# untitled.net
KiCad netlist of a schematic drawn in EAGLE
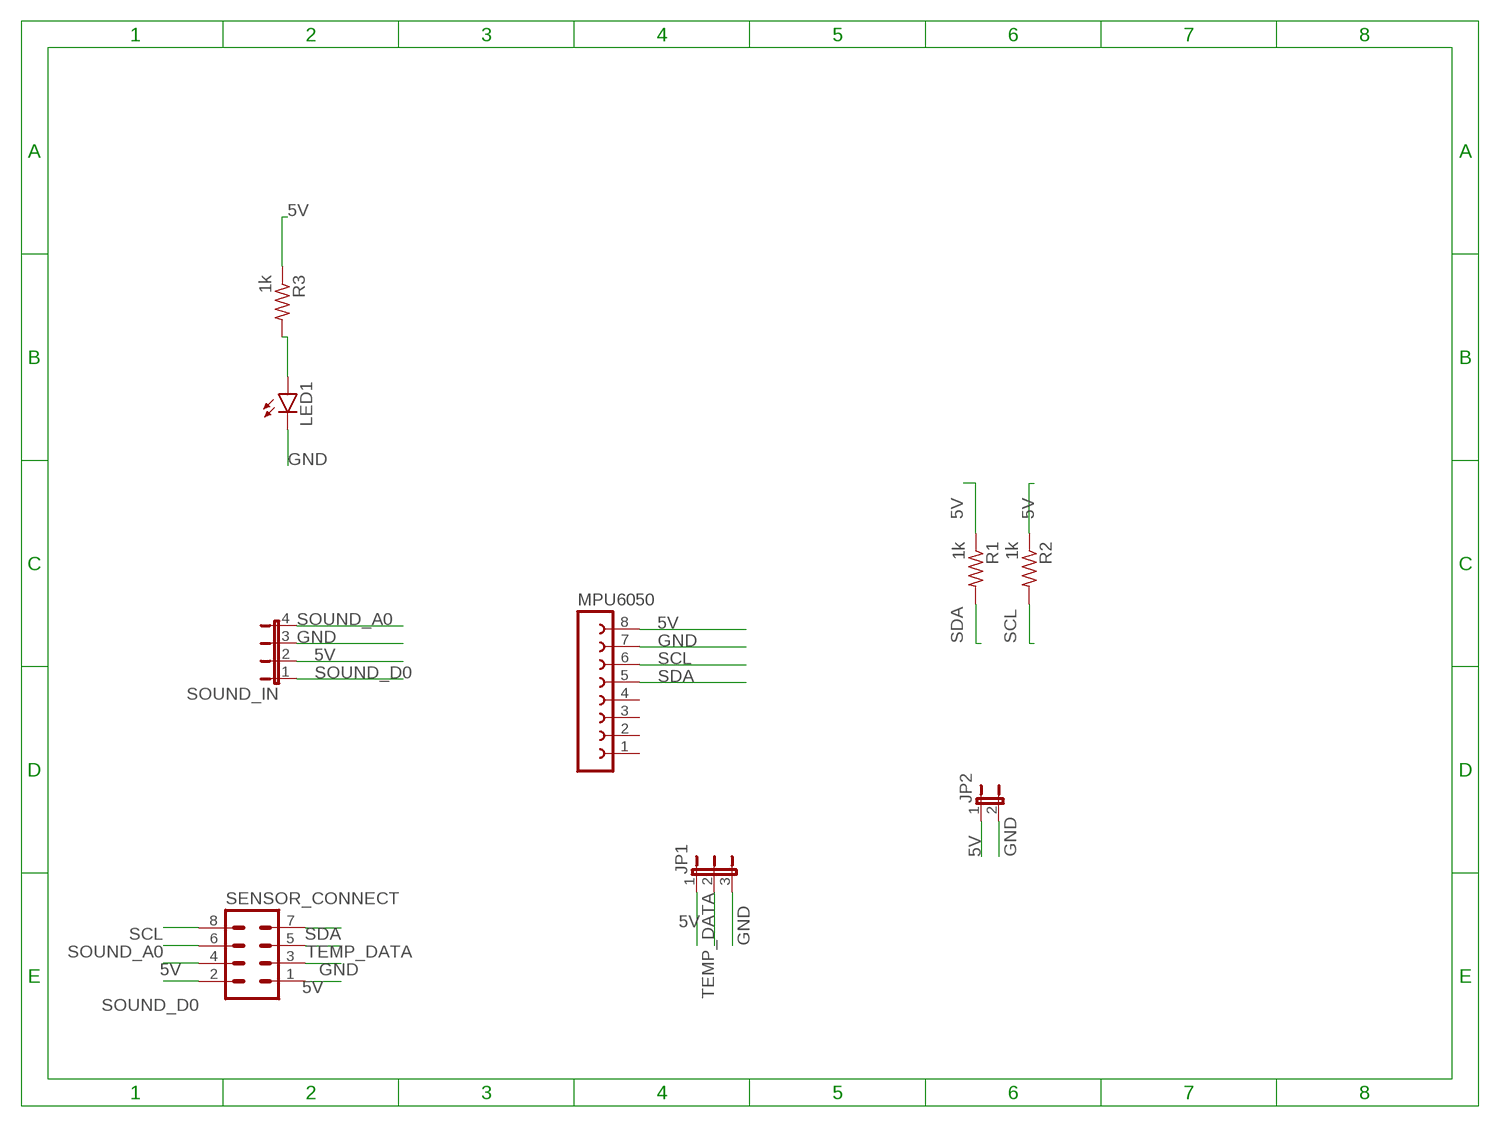
[diagram p0: schematic, sheet 1]

(export (version "E")
  (design (tool "Eeschema 10.0.6"))
  (components
    (comp (ref "JP1")
      (value "JP2W")
      (footprint "eagle-import:JP2W")
      (libsource (lib "eagle-import") (part "JP2W"))
    )
    (comp (ref "JP2")
      (value "JP1E")
      (footprint "eagle-import:JP1")
      (libsource (lib "eagle-import") (part "JP1E"))
    )
    (comp (ref "LED1")
      (value "LEDCHIP-LED0805")
      (footprint "eagle-import:CHIP-LED0805")
      (libsource (lib "eagle-import") (part "LEDCHIP-LED0805"))
    )
    (comp (ref "MPU6050")
      (value "FE08-1")
      (footprint "eagle-import:FE08")
      (libsource (lib "eagle-import") (part "FE08-1"))
    )
    (comp (ref "R1")
      (value "1k")
      (footprint "eagle-import:M0805")
      (libsource (lib "eagle-import") (part "R-US_M0805"))
    )
    (comp (ref "R2")
      (value "1k")
      (footprint "eagle-import:M0805")
      (libsource (lib "eagle-import") (part "R-US_M0805"))
    )
    (comp (ref "R3")
      (value "1k")
      (footprint "eagle-import:M0805")
      (libsource (lib "eagle-import") (part "R-US_M0805"))
    )
    (comp (ref "SENSOR_CONNECT")
      (value "MA04-2")
      (footprint "eagle-import:MA04-2")
      (libsource (lib "eagle-import") (part "MA04-2"))
    )
    (comp (ref "SOUND_IN")
      (value "JP4E")
      (footprint "eagle-import:JP4")
      (libsource (lib "eagle-import") (part "JP4E"))
    )
  )
  (nets
    (net (code "1") (name "/5V") (class "Default")
      (node (ref "JP1") (pin "1") (pinfunction "1_1") (pintype "passive"))
      (node (ref "JP2") (pin "1") (pinfunction "1_1") (pintype "passive"))
      (node (ref "MPU6050") (pin "8") (pinfunction "8_8") (pintype "passive"))
      (node (ref "R1") (pin "1") (pinfunction "1_1") (pintype "passive"))
      (node (ref "R2") (pin "1") (pinfunction "1_1") (pintype "passive"))
      (node (ref "R3") (pin "1") (pinfunction "1_1") (pintype "passive"))
      (node (ref "SENSOR_CONNECT") (pin "1") (pinfunction "1_1") (pintype "passive"))
      (node (ref "SENSOR_CONNECT") (pin "4") (pinfunction "4_4") (pintype "passive"))
      (node (ref "SOUND_IN") (pin "2") (pinfunction "2_2") (pintype "passive"))
    )
    (net (code "2") (name "/GND") (class "Default")
      (node (ref "JP1") (pin "3") (pinfunction "3_3") (pintype "passive"))
      (node (ref "JP2") (pin "2") (pinfunction "2_2") (pintype "passive"))
      (node (ref "LED1") (pin "C") (pinfunction "C_C") (pintype "passive"))
      (node (ref "MPU6050") (pin "7") (pinfunction "7_7") (pintype "passive"))
      (node (ref "SENSOR_CONNECT") (pin "3") (pinfunction "3_3") (pintype "passive"))
      (node (ref "SOUND_IN") (pin "3") (pinfunction "3_3") (pintype "passive"))
    )
    (net (code "3") (name "/SCL") (class "Default")
      (node (ref "MPU6050") (pin "6") (pinfunction "6_6") (pintype "passive"))
      (node (ref "R2") (pin "2") (pinfunction "2_2") (pintype "passive"))
      (node (ref "SENSOR_CONNECT") (pin "8") (pinfunction "8_8") (pintype "passive"))
    )
    (net (code "4") (name "/SDA") (class "Default")
      (node (ref "MPU6050") (pin "5") (pinfunction "5_5") (pintype "passive"))
      (node (ref "R1") (pin "2") (pinfunction "2_2") (pintype "passive"))
      (node (ref "SENSOR_CONNECT") (pin "7") (pinfunction "7_7") (pintype "passive"))
    )
    (net (code "5") (name "/SOUND_A0") (class "Default")
      (node (ref "SENSOR_CONNECT") (pin "6") (pinfunction "6_6") (pintype "passive"))
      (node (ref "SOUND_IN") (pin "4") (pinfunction "4_4") (pintype "passive"))
    )
    (net (code "6") (name "/SOUND_D0") (class "Default")
      (node (ref "SENSOR_CONNECT") (pin "2") (pinfunction "2_2") (pintype "passive"))
      (node (ref "SOUND_IN") (pin "1") (pinfunction "1_1") (pintype "passive"))
    )
    (net (code "7") (name "/TEMP_DATA") (class "Default")
      (node (ref "JP1") (pin "2") (pinfunction "2_2") (pintype "passive"))
      (node (ref "SENSOR_CONNECT") (pin "5") (pinfunction "5_5") (pintype "passive"))
    )
    (net (code "8") (name "Net-(LED1-PadA)") (class "Default")
      (node (ref "LED1") (pin "A") (pinfunction "A_A") (pintype "passive"))
      (node (ref "R3") (pin "2") (pinfunction "2_2") (pintype "passive"))
    )
    (net (code "9") (name "unconnected-(MPU6050-Pad1)") (class "Default")
      (node (ref "MPU6050") (pin "1") (pinfunction "1_1") (pintype "passive"))
    )
    (net (code "10") (name "unconnected-(MPU6050-Pad2)") (class "Default")
      (node (ref "MPU6050") (pin "2") (pinfunction "2_2") (pintype "passive"))
    )
    (net (code "11") (name "unconnected-(MPU6050-Pad3)") (class "Default")
      (node (ref "MPU6050") (pin "3") (pinfunction "3_3") (pintype "passive"))
    )
    (net (code "12") (name "unconnected-(MPU6050-Pad4)") (class "Default")
      (node (ref "MPU6050") (pin "4") (pinfunction "4_4") (pintype "passive"))
    )
  )
)
